# ARC-S-MOTOR.net
KiCad netlist of a schematic drawn in Altium Designer
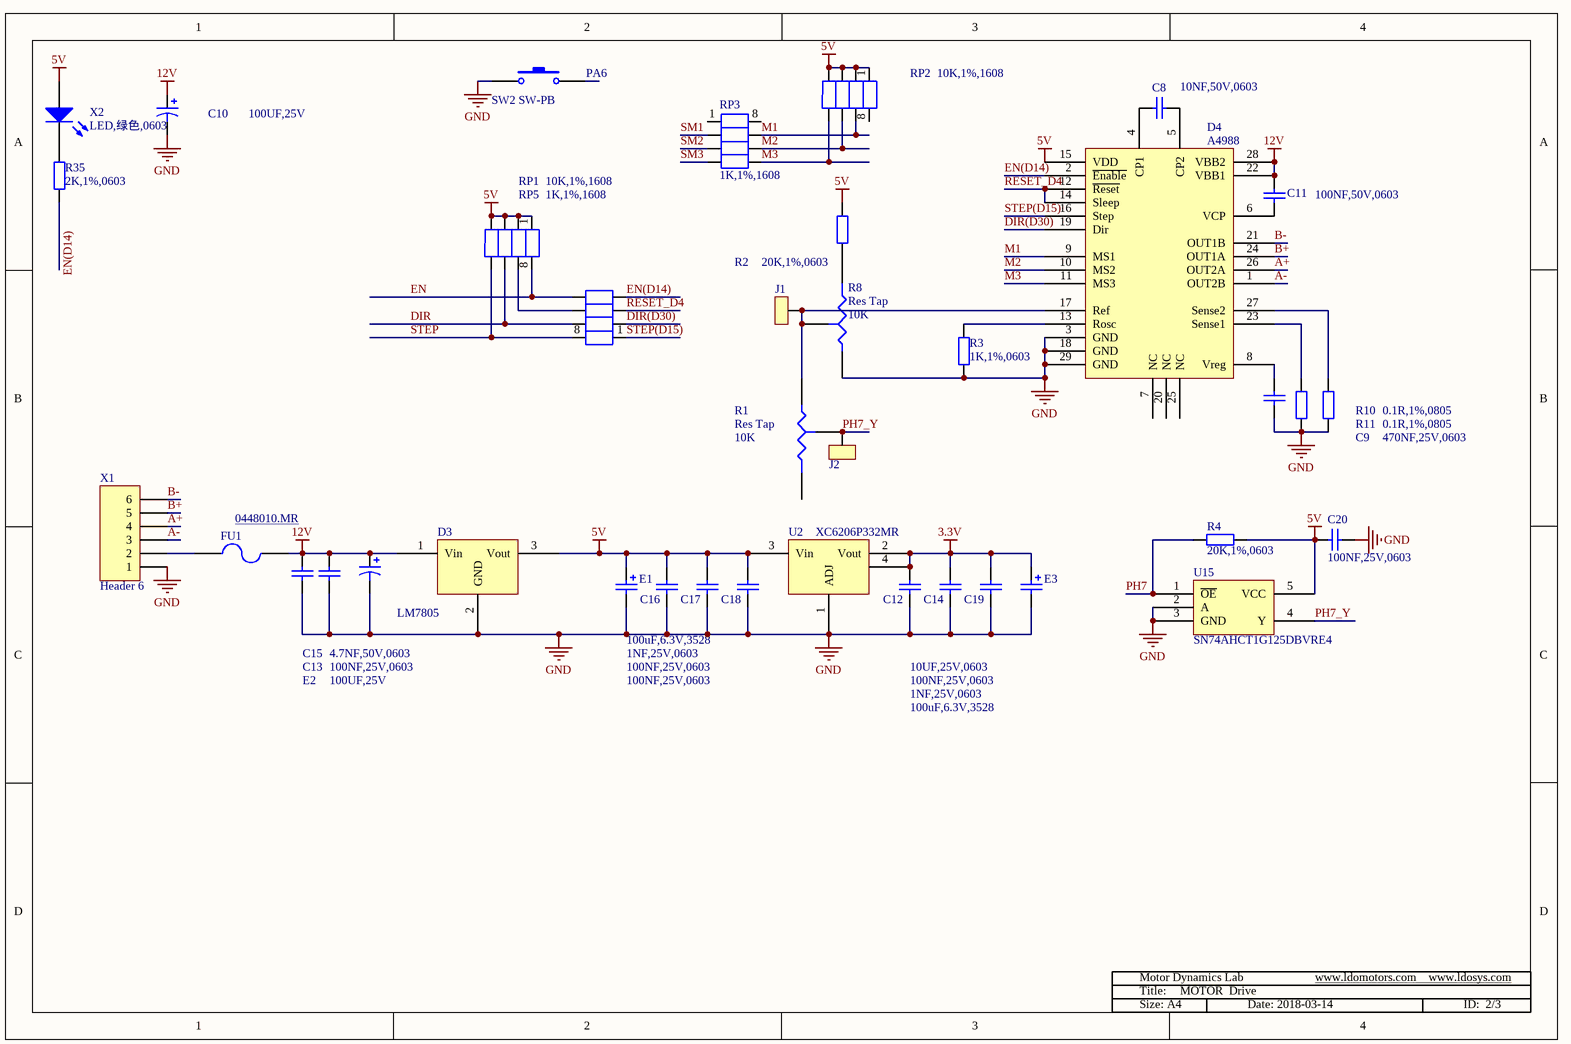
[diagram p0: ARC-S-MOTOR.SchDoc]

(export (version "E")
  (design (tool "Eeschema 10.0.6"))
  (components
    (comp (ref "C8")
      (value "10NF,50V,0603")
      (footprint "RC0603")
      (description "Capacitor")
      (fields (field (name "PUBLISHER") "Altium Limited"))
      (libsource (lib "Miscellaneous Devices") (part "Cap"))
    )
    (comp (ref "C9")
      (value "470NF,25V,0603")
      (footprint "RC0603")
      (description "Capacitor")
      (fields (field (name "PUBLISHER") "Altium Limited"))
      (libsource (lib "Miscellaneous Devices") (part "Cap"))
    )
    (comp (ref "C10")
      (value "100UF,25V")
      (footprint "EC-5X5.3")
      (description "Polarized Capacitor (Surface Mount)")
      (fields (field (name "PUBLISHER") "Altium Limited"))
      (libsource (lib "Miscellaneous Devices") (part "Cap Pol3"))
    )
    (comp (ref "C11")
      (value "100NF,50V,0603")
      (footprint "RC0603")
      (description "Capacitor")
      (fields (field (name "PUBLISHER") "Altium Limited"))
      (libsource (lib "Miscellaneous Devices") (part "Cap"))
    )
    (comp (ref "C12")
      (value "100NF,25V,0603")
      (footprint "RC0603")
      (description "Capacitor")
      (fields (field (name "PUBLISHER") "Altium Limited"))
      (libsource (lib "Miscellaneous Devices") (part "Cap"))
    )
    (comp (ref "C13")
      (value "100NF,25V,0603")
      (footprint "RC0603")
      (description "Capacitor")
      (fields (field (name "PUBLISHER") "Altium Limited"))
      (libsource (lib "Miscellaneous Devices") (part "Cap"))
    )
    (comp (ref "C14")
      (value "10UF,25V,0603")
      (footprint "RC0603")
      (description "Capacitor")
      (fields (field (name "PUBLISHER") "Altium Limited"))
      (libsource (lib "Miscellaneous Devices") (part "Cap"))
    )
    (comp (ref "C15")
      (value "4.7NF,50V,0603")
      (footprint "RC0603")
      (description "Capacitor")
      (fields (field (name "PUBLISHER") "Altium Limited"))
      (libsource (lib "Miscellaneous Devices") (part "Cap"))
    )
    (comp (ref "C16")
      (value "1NF,25V,0603")
      (footprint "RC0603")
      (description "Capacitor")
      (fields (field (name "PUBLISHER") "Altium Limited"))
      (libsource (lib "Miscellaneous Devices") (part "Cap"))
    )
    (comp (ref "C17")
      (value "100NF,25V,0603")
      (footprint "RC0603")
      (description "Capacitor")
      (fields (field (name "PUBLISHER") "Altium Limited"))
      (libsource (lib "Miscellaneous Devices") (part "Cap"))
    )
    (comp (ref "C18")
      (value "100NF,25V,0603")
      (footprint "RC0603")
      (description "Capacitor")
      (fields (field (name "PUBLISHER") "Altium Limited"))
      (libsource (lib "Miscellaneous Devices") (part "Cap"))
    )
    (comp (ref "C19")
      (value "1NF,25V,0603")
      (footprint "RC0603")
      (description "Capacitor")
      (fields (field (name "PUBLISHER") "Altium Limited"))
      (libsource (lib "Miscellaneous Devices") (part "Cap"))
    )
    (comp (ref "C20")
      (value "100NF,25V,0603")
      (footprint "RC0603")
      (description "Capacitor")
      (fields (field (name "PUBLISHER") "Altium Limited"))
      (libsource (lib "Miscellaneous Devices") (part "Cap"))
    )
    (comp (ref "D3") (value "LM7805") (footprint "78MXX") (libsource (lib "LDO原理图库") (part "LM78XX")))
    (comp (ref "D4") (value "A4988") (footprint "QFN-28-M") (libsource (lib "LDO原理图库") (part "A4988")))
    (comp (ref "E1")
      (value "100uF,6.3V,3528")
      (footprint "3528-21")
      (description "Polarized Capacitor (Axial)")
      (fields (field (name "PUBLISHER") "Altium Limited"))
      (libsource (lib "Miscellaneous Devices") (part "Cap Pol2"))
    )
    (comp (ref "E2")
      (value "100UF,25V")
      (footprint "EC-5X5.3")
      (description "Polarized Capacitor (Surface Mount)")
      (fields (field (name "PUBLISHER") "Altium Limited"))
      (libsource (lib "Miscellaneous Devices") (part "Cap Pol3"))
    )
    (comp (ref "E3")
      (value "100uF,6.3V,3528")
      (footprint "3528-21")
      (description "Polarized Capacitor (Axial)")
      (fields (field (name "PUBLISHER") "Altium Limited"))
      (libsource (lib "Miscellaneous Devices") (part "Cap Pol2"))
    )
    (comp (ref "FU1")
      (value "0448010.MR")
      (description "Fuse")
      (fields (field (name "PUBLISHER") "Altium Limited"))
      (libsource (lib "Miscellaneous Devices") (part "Fuse 2"))
    )
    (comp (ref "J1") (value "测试点") (footprint "test") (libsource (lib "") (part "测试点_1")))
    (comp (ref "J2") (value "测试点") (footprint "test") (libsource (lib "LDO原理图库") (part "测试点")))
    (comp (ref "R1")
      (value "Res Tap")
      (description "Tapped Resistor")
      (fields (field (name "ALTIUM_VALUE") "10K") (field (name "PUBLISHER") "Altium Limited"))
      (libsource (lib "Miscellaneous Devices") (part "Res Tap"))
    )
    (comp (ref "R2")
      (value "20K,1%,0603")
      (footprint "RC0603")
      (description "Resistor")
      (fields (field (name "PUBLISHER") "Altium Limited"))
      (libsource (lib "") (part "Res2_1"))
    )
    (comp (ref "R3")
      (value "1K,1%,0603")
      (footprint "RC0603")
      (description "Resistor")
      (fields (field (name "PUBLISHER") "Altium Limited"))
      (libsource (lib "Miscellaneous Devices") (part "Res2"))
    )
    (comp (ref "R4")
      (value "20K,1%,0603")
      (footprint "RC0603")
      (description "Resistor")
      (fields (field (name "PUBLISHER") "Altium Limited"))
      (libsource (lib "") (part "Res2_2"))
    )
    (comp (ref "R8")
      (value "Res Tap")
      (description "Tapped Resistor")
      (fields (field (name "ALTIUM_VALUE") "10K") (field (name "PUBLISHER") "Altium Limited"))
      (libsource (lib "Miscellaneous Devices") (part "Res Tap"))
    )
    (comp (ref "R10")
      (value "0.1R,1%,0805")
      (footprint "RC0805")
      (description "Resistor")
      (fields (field (name "PUBLISHER") "Altium Limited"))
      (libsource (lib "Miscellaneous Devices") (part "Res2"))
    )
    (comp (ref "R11")
      (value "0.1R,1%,0805")
      (footprint "RC0805")
      (description "Resistor")
      (fields (field (name "PUBLISHER") "Altium Limited"))
      (libsource (lib "Miscellaneous Devices") (part "Res2"))
    )
    (comp (ref "R35")
      (value "2K,1%,0603")
      (footprint "RC0603")
      (description "Resistor")
      (fields (field (name "PUBLISHER") "Altium Limited"))
      (libsource (lib "Miscellaneous Devices") (part "Res2"))
    )
    (comp (ref "RP1")
      (value "10K,1%,1608")
      (footprint "RP1608")
      (libsource (lib "LDO原理图库") (part "RP1608-1"))
    )
    (comp (ref "RP2")
      (value "10K,1%,1608")
      (footprint "RP1608")
      (libsource (lib "LDO原理图库") (part "RP1608-1"))
    )
    (comp (ref "RP3") (value "1K,1%,1608") (footprint "RP1608") (libsource (lib "LDO原理图库") (part "RP1608-1")))
    (comp (ref "RP5") (value "1K,1%,1608") (footprint "RP1608") (libsource (lib "LDO原理图库") (part "RP1608-1")))
    (comp (ref "SW2")
      (value "SW-PB")
      (footprint "SW-180")
      (description "Switch")
      (fields (field (name "PUBLISHER") "Altium Limited"))
      (libsource (lib "Miscellaneous Devices") (part "SW-PB"))
    )
    (comp (ref "U2")
      (value "XC6206P332MR")
      (footprint "SOT-23")
      (libsource (lib "AMS1117") (part "AMS1117-3.3"))
    )
    (comp (ref "U15")
      (value "SN74AHCT1G125DBVRE4")
      (footprint "SOT-23-5")
      (libsource (lib "LDO原理图库") (part "74AHCT1G125"))
    )
    (comp (ref "X1")
      (value "Header 6")
      (footprint "DIP-6-2.5")
      (description "Header, 6-Pin")
      (fields (field (name "PUBLISHER") "Altium Limited"))
      (libsource (lib "Miscellaneous Connectors") (part "Header 6"))
    )
    (comp (ref "X2")
      (value "LED,绿色,0603")
      (footprint "LED-0603")
      (description "Typical INFRARED GaAs LED")
      (fields (field (name "PUBLISHER") "Altium Limited"))
      (libsource (lib "Miscellaneous Devices") (part "LED0"))
    )
  )
  (nets
    (net (code "1") (name "/A+") (class "Default")
      (node (ref "D4") (pin "26") (pinfunction "OUT2A_26") (pintype "passive"))
      (node (ref "X1") (pin "4") (pinfunction "4_4") (pintype "passive"))
    )
    (net (code "2") (name "/A-") (class "Default")
      (node (ref "D4") (pin "1") (pinfunction "OUT2B_1") (pintype "passive"))
      (node (ref "X1") (pin "3") (pinfunction "3_3") (pintype "passive"))
    )
    (net (code "3") (name "/B+") (class "Default")
      (node (ref "D4") (pin "24") (pinfunction "OUT1A_24") (pintype "passive"))
      (node (ref "X1") (pin "5") (pinfunction "5_5") (pintype "passive"))
    )
    (net (code "4") (name "/B-") (class "Default")
      (node (ref "D4") (pin "21") (pinfunction "OUT1B_21") (pintype "passive"))
      (node (ref "X1") (pin "6") (pinfunction "6_6") (pintype "passive"))
    )
    (net (code "5") (name "/DIR") (class "Default")
      (node (ref "RP1") (pin "6") (pintype "passive"))
      (node (ref "RP5") (pin "7") (pintype "passive"))
    )
    (net (code "6") (name "/DIR(D30)") (class "Default")
      (node (ref "D4") (pin "19") (pinfunction "Dir_19") (pintype "passive"))
      (node (ref "RP5") (pin "2") (pintype "passive"))
    )
    (net (code "7") (name "/EN") (class "Default")
      (node (ref "RP1") (pin "8") (pintype "passive"))
      (node (ref "RP5") (pin "5") (pintype "passive"))
    )
    (net (code "8") (name "/EN(D14)") (class "Default")
      (node (ref "D4") (pin "2") (pinfunction "~{Enable}_2") (pintype "passive"))
      (node (ref "R35") (pin "1") (pinfunction "1_1") (pintype "passive"))
      (node (ref "RP5") (pin "4") (pintype "passive"))
    )
    (net (code "9") (name "/M1") (class "Default")
      (node (ref "D4") (pin "9") (pinfunction "MS1_9") (pintype "passive"))
      (node (ref "RP2") (pin "7") (pintype "passive"))
      (node (ref "RP3") (pin "7") (pintype "passive"))
    )
    (net (code "10") (name "/M2") (class "Default")
      (node (ref "D4") (pin "10") (pinfunction "MS2_10") (pintype "passive"))
      (node (ref "RP2") (pin "6") (pintype "passive"))
      (node (ref "RP3") (pin "6") (pintype "passive"))
    )
    (net (code "11") (name "/M3") (class "Default")
      (node (ref "D4") (pin "11") (pinfunction "MS3_11") (pintype "passive"))
      (node (ref "RP2") (pin "5") (pintype "passive"))
      (node (ref "RP3") (pin "5") (pintype "passive"))
    )
    (net (code "12") (name "/PA6") (class "Default")
      (node (ref "SW2") (pin "2") (pinfunction "2_2") (pintype "passive"))
    )
    (net (code "13") (name "/PH7") (class "Default")
      (node (ref "R4") (pin "1") (pinfunction "1_1") (pintype "passive"))
      (node (ref "U15") (pin "1") (pinfunction "~{OE}_1") (pintype "passive"))
    )
    (net (code "14") (name "/PH7_Y") (class "Default")
      (node (ref "J2") (pin "1") (pinfunction "1_1") (pintype "passive"))
      (node (ref "R1") (pin "3") (pinfunction "TAP_3") (pintype "passive"))
      (node (ref "U15") (pin "4") (pinfunction "Y_4") (pintype "passive"))
    )
    (net (code "15") (name "/RESET_D4") (class "Default")
      (node (ref "D4") (pin "12") (pinfunction "~{Reset}_12") (pintype "passive"))
      (node (ref "D4") (pin "14") (pinfunction "Sleep_14") (pintype "passive"))
      (node (ref "RP5") (pin "3") (pintype "passive"))
    )
    (net (code "16") (name "/SM1") (class "Default") (node (ref "RP3") (pin "2") (pintype "passive")))
    (net (code "17") (name "/SM2") (class "Default") (node (ref "RP3") (pin "3") (pintype "passive")))
    (net (code "18") (name "/SM3") (class "Default") (node (ref "RP3") (pin "4") (pintype "passive")))
    (net (code "19") (name "/STEP") (class "Default")
      (node (ref "RP1") (pin "5") (pintype "passive"))
      (node (ref "RP5") (pin "8") (pintype "passive"))
    )
    (net (code "20") (name "/STEP(D15)") (class "Default")
      (node (ref "D4") (pin "16") (pinfunction "Step_16") (pintype "passive"))
      (node (ref "RP5") (pin "1") (pintype "passive"))
    )
    (net (code "21") (name "3.3V") (class "Default")
      (node (ref "C12") (pin "2") (pinfunction "2_2") (pintype "passive"))
      (node (ref "C14") (pin "2") (pinfunction "2_2") (pintype "passive"))
      (node (ref "C19") (pin "2") (pinfunction "2_2") (pintype "passive"))
      (node (ref "E3") (pin "1") (pinfunction "1_1") (pintype "passive"))
      (node (ref "U2") (pin "2") (pinfunction "Vout_2") (pintype "passive"))
      (node (ref "U2") (pin "4") (pinfunction "4_4") (pintype "passive"))
    )
    (net (code "22") (name "5V") (class "Default")
      (node (ref "C16") (pin "2") (pinfunction "2_2") (pintype "passive"))
      (node (ref "C17") (pin "2") (pinfunction "2_2") (pintype "passive"))
      (node (ref "C18") (pin "2") (pinfunction "2_2") (pintype "passive"))
      (node (ref "C20") (pin "1") (pinfunction "1_1") (pintype "passive"))
      (node (ref "D3") (pin "3") (pinfunction "Vout_3") (pintype "passive"))
      (node (ref "D4") (pin "15") (pinfunction "VDD_15") (pintype "passive"))
      (node (ref "E1") (pin "1") (pinfunction "1_1") (pintype "passive"))
      (node (ref "R2") (pin "1") (pinfunction "1_1") (pintype "passive"))
      (node (ref "R4") (pin "2") (pinfunction "2_2") (pintype "passive"))
      (node (ref "RP1") (pin "1") (pintype "passive"))
      (node (ref "RP1") (pin "2") (pintype "passive"))
      (node (ref "RP1") (pin "3") (pintype "passive"))
      (node (ref "RP1") (pin "4") (pintype "passive"))
      (node (ref "RP2") (pin "1") (pintype "passive"))
      (node (ref "RP2") (pin "2") (pintype "passive"))
      (node (ref "RP2") (pin "3") (pintype "passive"))
      (node (ref "RP2") (pin "4") (pintype "passive"))
      (node (ref "U15") (pin "5") (pinfunction "VCC_5") (pintype "passive"))
      (node (ref "U2") (pin "3") (pinfunction "Vin_3") (pintype "passive"))
      (node (ref "X2") (pin "1") (pinfunction "A_1") (pintype "passive"))
    )
    (net (code "23") (name "12V") (class "Default")
      (node (ref "C10") (pin "1") (pinfunction "1_1") (pintype "passive"))
      (node (ref "C11") (pin "2") (pinfunction "2_2") (pintype "passive"))
      (node (ref "C13") (pin "1") (pinfunction "1_1") (pintype "passive"))
      (node (ref "C15") (pin "2") (pinfunction "2_2") (pintype "passive"))
      (node (ref "D3") (pin "1") (pinfunction "Vin_1") (pintype "passive"))
      (node (ref "D4") (pin "22") (pinfunction "VBB1_22") (pintype "passive"))
      (node (ref "D4") (pin "28") (pinfunction "VBB2_28") (pintype "passive"))
      (node (ref "E2") (pin "1") (pinfunction "1_1") (pintype "passive"))
      (node (ref "FU1") (pin "2") (pinfunction "2_2") (pintype "passive"))
    )
    (net (code "24") (name "GND") (class "Default")
      (node (ref "C10") (pin "2") (pinfunction "2_2") (pintype "passive"))
      (node (ref "C12") (pin "1") (pinfunction "1_1") (pintype "passive"))
      (node (ref "C13") (pin "2") (pinfunction "2_2") (pintype "passive"))
      (node (ref "C14") (pin "1") (pinfunction "1_1") (pintype "passive"))
      (node (ref "C15") (pin "1") (pinfunction "1_1") (pintype "passive"))
      (node (ref "C16") (pin "1") (pinfunction "1_1") (pintype "passive"))
      (node (ref "C17") (pin "1") (pinfunction "1_1") (pintype "passive"))
      (node (ref "C18") (pin "1") (pinfunction "1_1") (pintype "passive"))
      (node (ref "C19") (pin "1") (pinfunction "1_1") (pintype "passive"))
      (node (ref "C20") (pin "2") (pinfunction "2_2") (pintype "passive"))
      (node (ref "C9") (pin "1") (pinfunction "1_1") (pintype "passive"))
      (node (ref "D3") (pin "2") (pinfunction "GND_2") (pintype "passive"))
      (node (ref "D4") (pin "18") (pinfunction "GND_18") (pintype "passive"))
      (node (ref "D4") (pin "29") (pinfunction "GND_29") (pintype "passive"))
      (node (ref "D4") (pin "3") (pinfunction "GND_3") (pintype "passive"))
      (node (ref "E1") (pin "2") (pinfunction "2_2") (pintype "passive"))
      (node (ref "E2") (pin "2") (pinfunction "2_2") (pintype "passive"))
      (node (ref "E3") (pin "2") (pinfunction "2_2") (pintype "passive"))
      (node (ref "R10") (pin "1") (pinfunction "1_1") (pintype "passive"))
      (node (ref "R11") (pin "1") (pinfunction "1_1") (pintype "passive"))
      (node (ref "R3") (pin "1") (pinfunction "1_1") (pintype "passive"))
      (node (ref "R8") (pin "1") (pinfunction "A_1") (pintype "passive"))
      (node (ref "SW2") (pin "1") (pinfunction "1_1") (pintype "passive"))
      (node (ref "U15") (pin "2") (pinfunction "A_2") (pintype "passive"))
      (node (ref "U15") (pin "3") (pinfunction "GND_3") (pintype "passive"))
      (node (ref "U2") (pin "1") (pinfunction "ADJ_1") (pintype "passive"))
      (node (ref "X1") (pin "1") (pinfunction "1_1") (pintype "passive"))
    )
    (net (code "25") (name "Net-(D4-CP1)") (class "Default")
      (node (ref "C8") (pin "1") (pinfunction "1_1") (pintype "passive"))
      (node (ref "D4") (pin "4") (pinfunction "CP1_4") (pintype "passive"))
    )
    (net (code "26") (name "Net-(D4-CP2)") (class "Default")
      (node (ref "C8") (pin "2") (pinfunction "2_2") (pintype "passive"))
      (node (ref "D4") (pin "5") (pinfunction "CP2_5") (pintype "passive"))
    )
    (net (code "27") (name "Net-(D4-Ref)") (class "Default")
      (node (ref "D4") (pin "17") (pinfunction "Ref_17") (pintype "passive"))
      (node (ref "J1") (pin "1") (pinfunction "1_1") (pintype "passive"))
      (node (ref "R1") (pin "1") (pinfunction "A_1") (pintype "passive"))
      (node (ref "R8") (pin "3") (pinfunction "TAP_3") (pintype "passive"))
    )
    (net (code "28") (name "Net-(D4-Rosc)") (class "Default")
      (node (ref "D4") (pin "13") (pinfunction "Rosc_13") (pintype "passive"))
      (node (ref "R3") (pin "2") (pinfunction "2_2") (pintype "passive"))
    )
    (net (code "29") (name "Net-(D4-Sense1)") (class "Default")
      (node (ref "D4") (pin "23") (pinfunction "Sense1_23") (pintype "passive"))
      (node (ref "R10") (pin "2") (pinfunction "2_2") (pintype "passive"))
    )
    (net (code "30") (name "Net-(D4-Sense2)") (class "Default")
      (node (ref "D4") (pin "27") (pinfunction "Sense2_27") (pintype "passive"))
      (node (ref "R11") (pin "2") (pinfunction "2_2") (pintype "passive"))
    )
    (net (code "31") (name "Net-(D4-VCP)") (class "Default")
      (node (ref "C11") (pin "1") (pinfunction "1_1") (pintype "passive"))
      (node (ref "D4") (pin "6") (pinfunction "VCP_6") (pintype "passive"))
    )
    (net (code "32") (name "Net-(D4-Vreg)") (class "Default")
      (node (ref "C9") (pin "2") (pinfunction "2_2") (pintype "passive"))
      (node (ref "D4") (pin "8") (pinfunction "Vreg_8") (pintype "passive"))
    )
    (net (code "33") (name "Net-(FU1-Pad1)") (class "Default")
      (node (ref "FU1") (pin "1") (pinfunction "1_1") (pintype "passive"))
      (node (ref "X1") (pin "2") (pinfunction "2_2") (pintype "passive"))
    )
    (net (code "34") (name "Net-(R8-B)") (class "Default")
      (node (ref "R2") (pin "2") (pinfunction "2_2") (pintype "passive"))
      (node (ref "R8") (pin "2") (pinfunction "B_2") (pintype "passive"))
    )
    (net (code "35") (name "Net-(RP1-Pad7)") (class "Default")
      (node (ref "RP1") (pin "7") (pintype "passive"))
      (node (ref "RP5") (pin "6") (pintype "passive"))
    )
    (net (code "36") (name "Net-(X2-K)") (class "Default")
      (node (ref "R35") (pin "2") (pinfunction "2_2") (pintype "passive"))
      (node (ref "X2") (pin "2") (pinfunction "K_2") (pintype "passive"))
    )
    (net (code "37") (name "unconnected-(D4-NC-Pad7)") (class "Default")
      (node (ref "D4") (pin "7") (pinfunction "NC_7") (pintype "passive"))
    )
    (net (code "38") (name "unconnected-(D4-NC-Pad20)") (class "Default")
      (node (ref "D4") (pin "20") (pinfunction "NC_20") (pintype "passive"))
    )
    (net (code "39") (name "unconnected-(D4-NC-Pad25)") (class "Default")
      (node (ref "D4") (pin "25") (pinfunction "NC_25") (pintype "passive"))
    )
    (net (code "40") (name "unconnected-(R1-B-Pad2)") (class "Default")
      (node (ref "R1") (pin "2") (pinfunction "B_2") (pintype "passive"))
    )
    (net (code "41") (name "unconnected-(RP2-Pad8)") (class "Default")
      (node (ref "RP2") (pin "8") (pintype "passive"))
    )
    (net (code "42") (name "unconnected-(RP3-Pad1)") (class "Default")
      (node (ref "RP3") (pin "1") (pintype "passive"))
    )
    (net (code "43") (name "unconnected-(RP3-Pad8)") (class "Default")
      (node (ref "RP3") (pin "8") (pintype "passive"))
    )
  )
)
